# led_circuits.net
KiCad netlist of a schematic drawn in EAGLE
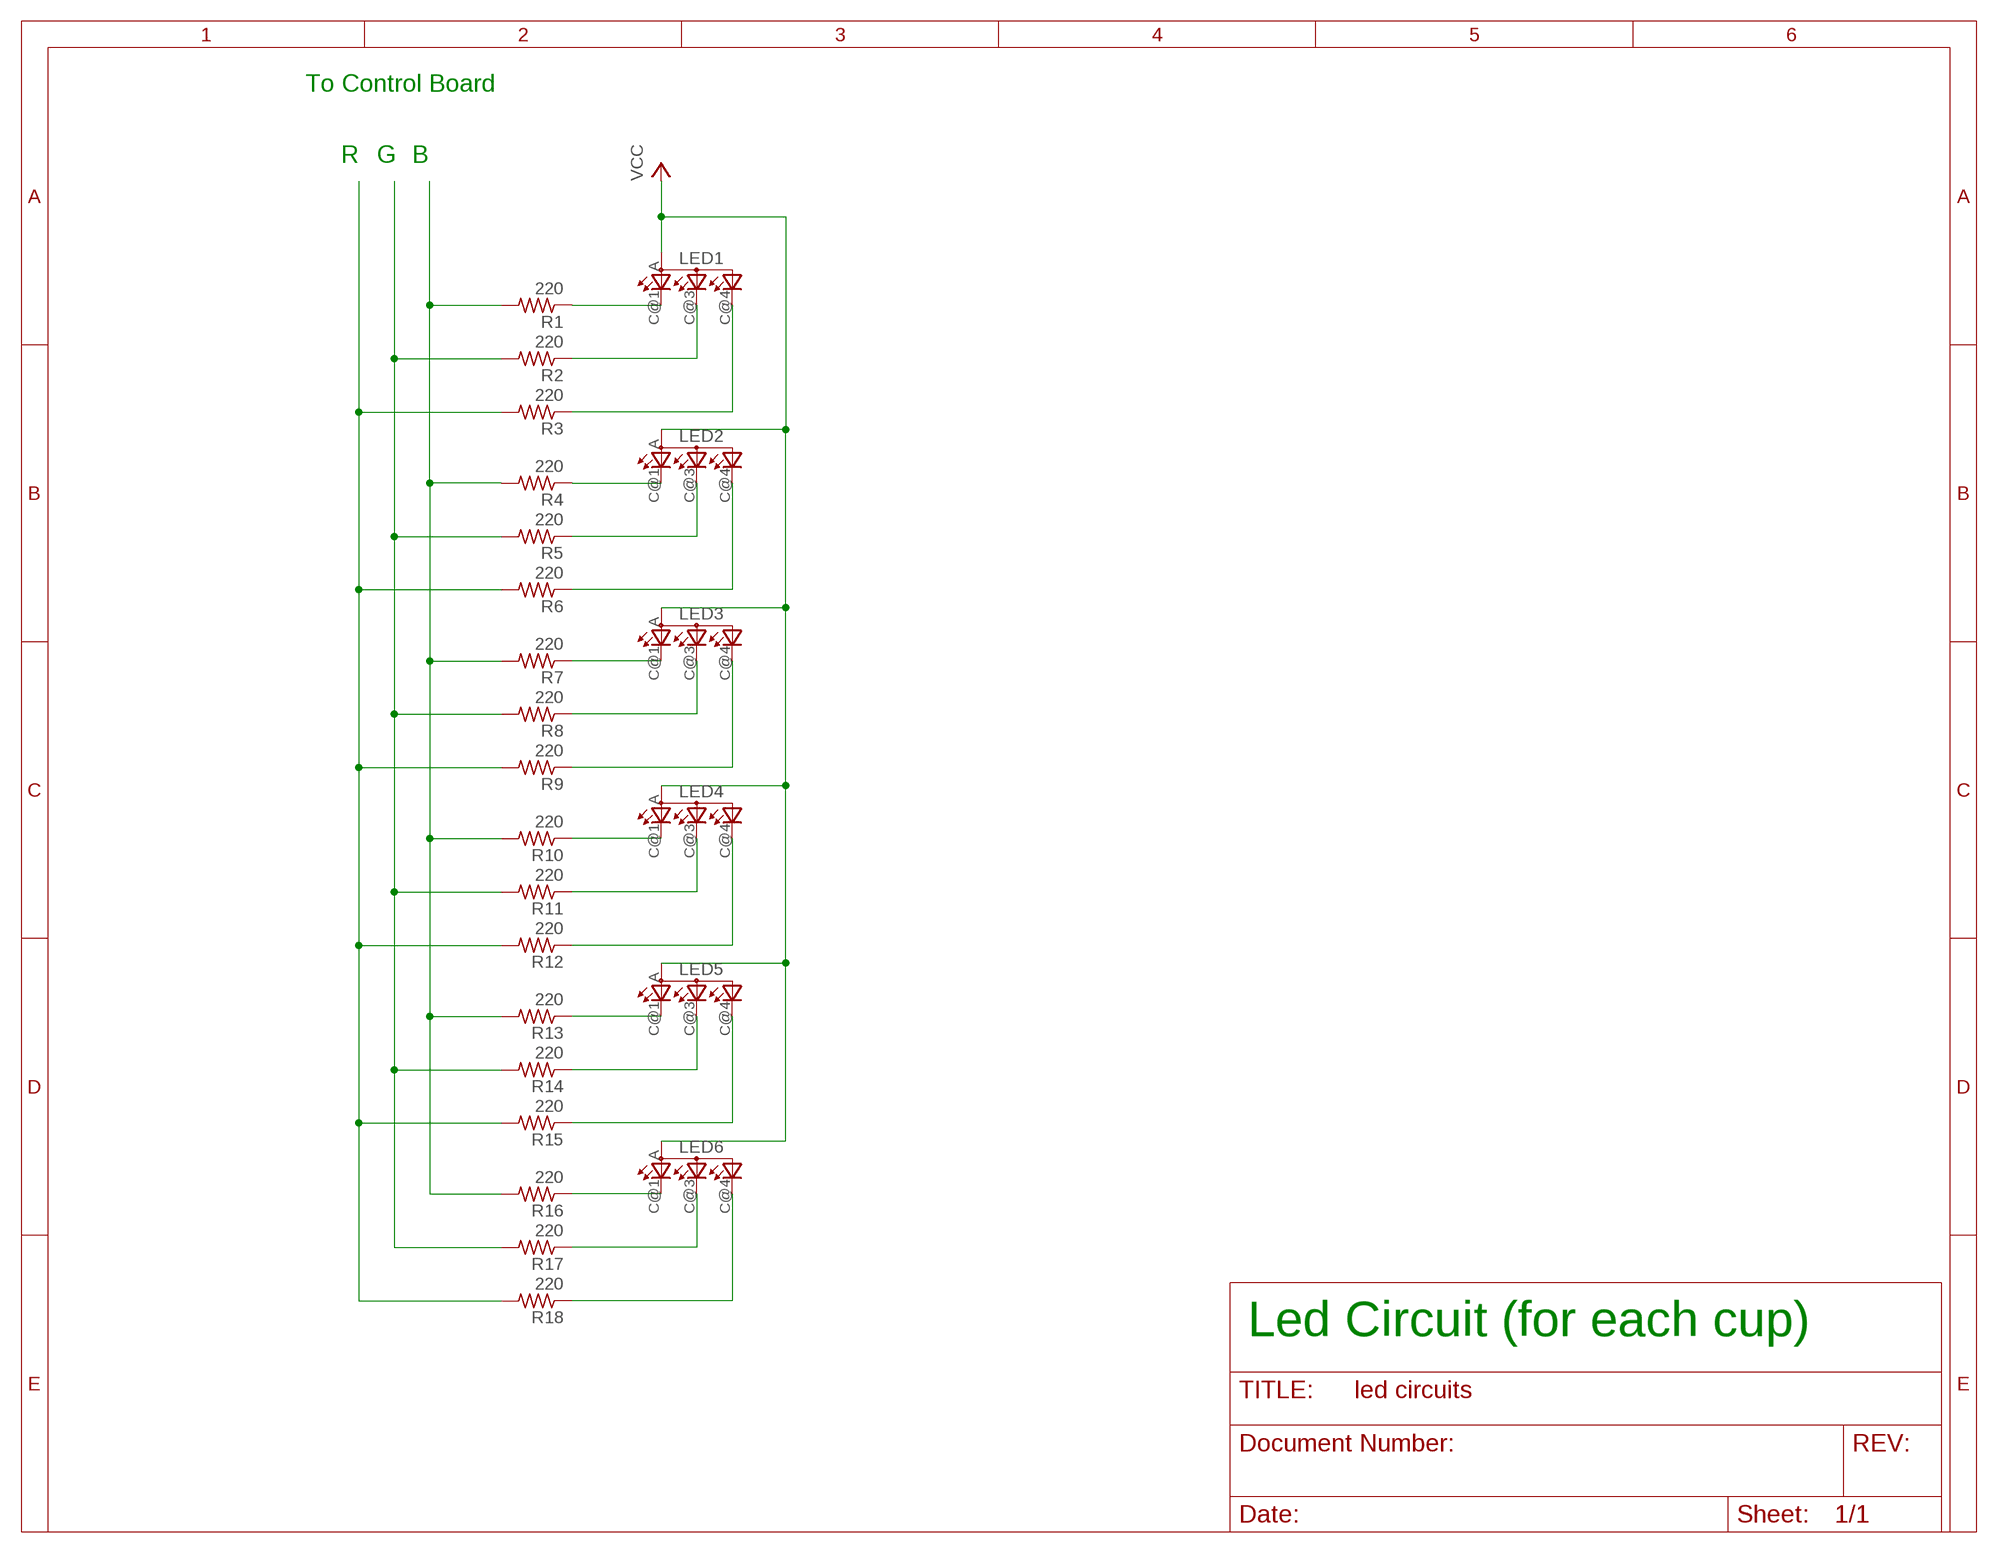
[diagram p0: schematic, sheet 1]

(export (version "E")
  (design (tool "Eeschema 10.0.6"))
  (components
    (comp (ref "LED1")
      (value "TOPLED-3P-LCC-4")
      (footprint "eagle-import:P-LCC-4")
      (libsource (lib "eagle-import") (part "TOPLED-3P-LCC-4"))
    )
    (comp (ref "LED2")
      (value "TOPLED-3P-LCC-4")
      (footprint "eagle-import:P-LCC-4")
      (libsource (lib "eagle-import") (part "TOPLED-3P-LCC-4"))
    )
    (comp (ref "LED3")
      (value "TOPLED-3P-LCC-4")
      (footprint "eagle-import:P-LCC-4")
      (libsource (lib "eagle-import") (part "TOPLED-3P-LCC-4"))
    )
    (comp (ref "LED4")
      (value "TOPLED-3P-LCC-4")
      (footprint "eagle-import:P-LCC-4")
      (libsource (lib "eagle-import") (part "TOPLED-3P-LCC-4"))
    )
    (comp (ref "LED5")
      (value "TOPLED-3P-LCC-4")
      (footprint "eagle-import:P-LCC-4")
      (libsource (lib "eagle-import") (part "TOPLED-3P-LCC-4"))
    )
    (comp (ref "LED6")
      (value "TOPLED-3P-LCC-4")
      (footprint "eagle-import:P-LCC-4")
      (libsource (lib "eagle-import") (part "TOPLED-3P-LCC-4"))
    )
    (comp (ref "R1")
      (value "220")
      (footprint "eagle-import:0207_2V")
      (libsource (lib "eagle-import") (part "R-US_0207/2V"))
    )
    (comp (ref "R2")
      (value "220")
      (footprint "eagle-import:0207_2V")
      (libsource (lib "eagle-import") (part "R-US_0207/2V"))
    )
    (comp (ref "R3")
      (value "220")
      (footprint "eagle-import:0207_2V")
      (libsource (lib "eagle-import") (part "R-US_0207/2V"))
    )
    (comp (ref "R4")
      (value "220")
      (footprint "eagle-import:0207_2V")
      (libsource (lib "eagle-import") (part "R-US_0207/2V"))
    )
    (comp (ref "R5")
      (value "220")
      (footprint "eagle-import:0207_2V")
      (libsource (lib "eagle-import") (part "R-US_0207/2V"))
    )
    (comp (ref "R6")
      (value "220")
      (footprint "eagle-import:0207_2V")
      (libsource (lib "eagle-import") (part "R-US_0207/2V"))
    )
    (comp (ref "R7")
      (value "220")
      (footprint "eagle-import:0207_2V")
      (libsource (lib "eagle-import") (part "R-US_0207/2V"))
    )
    (comp (ref "R8")
      (value "220")
      (footprint "eagle-import:0207_2V")
      (libsource (lib "eagle-import") (part "R-US_0207/2V"))
    )
    (comp (ref "R9")
      (value "220")
      (footprint "eagle-import:0207_2V")
      (libsource (lib "eagle-import") (part "R-US_0207/2V"))
    )
    (comp (ref "R10")
      (value "220")
      (footprint "eagle-import:0207_2V")
      (libsource (lib "eagle-import") (part "R-US_0207/2V"))
    )
    (comp (ref "R11")
      (value "220")
      (footprint "eagle-import:0207_2V")
      (libsource (lib "eagle-import") (part "R-US_0207/2V"))
    )
    (comp (ref "R12")
      (value "220")
      (footprint "eagle-import:0207_2V")
      (libsource (lib "eagle-import") (part "R-US_0207/2V"))
    )
    (comp (ref "R13")
      (value "220")
      (footprint "eagle-import:0207_2V")
      (libsource (lib "eagle-import") (part "R-US_0207/2V"))
    )
    (comp (ref "R14")
      (value "220")
      (footprint "eagle-import:0207_2V")
      (libsource (lib "eagle-import") (part "R-US_0207/2V"))
    )
    (comp (ref "R15")
      (value "220")
      (footprint "eagle-import:0207_2V")
      (libsource (lib "eagle-import") (part "R-US_0207/2V"))
    )
    (comp (ref "R16")
      (value "220")
      (footprint "eagle-import:0207_2V")
      (libsource (lib "eagle-import") (part "R-US_0207/2V"))
    )
    (comp (ref "R17")
      (value "220")
      (footprint "eagle-import:0207_2V")
      (libsource (lib "eagle-import") (part "R-US_0207/2V"))
    )
    (comp (ref "R18")
      (value "220")
      (footprint "eagle-import:0207_2V")
      (libsource (lib "eagle-import") (part "R-US_0207/2V"))
    )
  )
  (nets
    (net (code "1") (name "Net-(LED1-CBLUE)") (class "Default")
      (node (ref "LED1") (pin "C@3") (pinfunction "CBLUE_C@3") (pintype "passive"))
      (node (ref "R2") (pin "1") (pinfunction "1_1") (pintype "passive"))
    )
    (net (code "2") (name "Net-(LED1-CGREEN)") (class "Default")
      (node (ref "LED1") (pin "C@4") (pinfunction "CGREEN_C@4") (pintype "passive"))
      (node (ref "R3") (pin "1") (pinfunction "1_1") (pintype "passive"))
    )
    (net (code "3") (name "Net-(LED1-CRED)") (class "Default")
      (node (ref "LED1") (pin "C@1") (pinfunction "CRED_C@1") (pintype "passive"))
      (node (ref "R1") (pin "1") (pinfunction "1_1") (pintype "passive"))
    )
    (net (code "4") (name "Net-(LED2-CBLUE)") (class "Default")
      (node (ref "LED2") (pin "C@3") (pinfunction "CBLUE_C@3") (pintype "passive"))
      (node (ref "R5") (pin "1") (pinfunction "1_1") (pintype "passive"))
    )
    (net (code "5") (name "Net-(LED2-CGREEN)") (class "Default")
      (node (ref "LED2") (pin "C@4") (pinfunction "CGREEN_C@4") (pintype "passive"))
      (node (ref "R6") (pin "1") (pinfunction "1_1") (pintype "passive"))
    )
    (net (code "6") (name "Net-(LED2-CRED)") (class "Default")
      (node (ref "LED2") (pin "C@1") (pinfunction "CRED_C@1") (pintype "passive"))
      (node (ref "R4") (pin "1") (pinfunction "1_1") (pintype "passive"))
    )
    (net (code "7") (name "Net-(LED3-CBLUE)") (class "Default")
      (node (ref "LED3") (pin "C@3") (pinfunction "CBLUE_C@3") (pintype "passive"))
      (node (ref "R8") (pin "1") (pinfunction "1_1") (pintype "passive"))
    )
    (net (code "8") (name "Net-(LED3-CGREEN)") (class "Default")
      (node (ref "LED3") (pin "C@4") (pinfunction "CGREEN_C@4") (pintype "passive"))
      (node (ref "R9") (pin "1") (pinfunction "1_1") (pintype "passive"))
    )
    (net (code "9") (name "Net-(LED3-CRED)") (class "Default")
      (node (ref "LED3") (pin "C@1") (pinfunction "CRED_C@1") (pintype "passive"))
      (node (ref "R7") (pin "1") (pinfunction "1_1") (pintype "passive"))
    )
    (net (code "10") (name "Net-(LED4-CBLUE)") (class "Default")
      (node (ref "LED4") (pin "C@3") (pinfunction "CBLUE_C@3") (pintype "passive"))
      (node (ref "R11") (pin "1") (pinfunction "1_1") (pintype "passive"))
    )
    (net (code "11") (name "Net-(LED4-CGREEN)") (class "Default")
      (node (ref "LED4") (pin "C@4") (pinfunction "CGREEN_C@4") (pintype "passive"))
      (node (ref "R12") (pin "1") (pinfunction "1_1") (pintype "passive"))
    )
    (net (code "12") (name "Net-(LED4-CRED)") (class "Default")
      (node (ref "LED4") (pin "C@1") (pinfunction "CRED_C@1") (pintype "passive"))
      (node (ref "R10") (pin "1") (pinfunction "1_1") (pintype "passive"))
    )
    (net (code "13") (name "Net-(LED5-CBLUE)") (class "Default")
      (node (ref "LED5") (pin "C@3") (pinfunction "CBLUE_C@3") (pintype "passive"))
      (node (ref "R14") (pin "1") (pinfunction "1_1") (pintype "passive"))
    )
    (net (code "14") (name "Net-(LED5-CGREEN)") (class "Default")
      (node (ref "LED5") (pin "C@4") (pinfunction "CGREEN_C@4") (pintype "passive"))
      (node (ref "R15") (pin "1") (pinfunction "1_1") (pintype "passive"))
    )
    (net (code "15") (name "Net-(LED5-CRED)") (class "Default")
      (node (ref "LED5") (pin "C@1") (pinfunction "CRED_C@1") (pintype "passive"))
      (node (ref "R13") (pin "1") (pinfunction "1_1") (pintype "passive"))
    )
    (net (code "16") (name "Net-(LED6-CBLUE)") (class "Default")
      (node (ref "LED6") (pin "C@3") (pinfunction "CBLUE_C@3") (pintype "passive"))
      (node (ref "R17") (pin "1") (pinfunction "1_1") (pintype "passive"))
    )
    (net (code "17") (name "Net-(LED6-CGREEN)") (class "Default")
      (node (ref "LED6") (pin "C@4") (pinfunction "CGREEN_C@4") (pintype "passive"))
      (node (ref "R18") (pin "1") (pinfunction "1_1") (pintype "passive"))
    )
    (net (code "18") (name "Net-(LED6-CRED)") (class "Default")
      (node (ref "LED6") (pin "C@1") (pinfunction "CRED_C@1") (pintype "passive"))
      (node (ref "R16") (pin "1") (pinfunction "1_1") (pintype "passive"))
    )
    (net (code "19") (name "Net-(R1-Pad2)") (class "Default")
      (node (ref "R1") (pin "2") (pinfunction "2_2") (pintype "passive"))
      (node (ref "R10") (pin "2") (pinfunction "2_2") (pintype "passive"))
      (node (ref "R13") (pin "2") (pinfunction "2_2") (pintype "passive"))
      (node (ref "R16") (pin "2") (pinfunction "2_2") (pintype "passive"))
      (node (ref "R4") (pin "2") (pinfunction "2_2") (pintype "passive"))
      (node (ref "R7") (pin "2") (pinfunction "2_2") (pintype "passive"))
    )
    (net (code "20") (name "Net-(R11-Pad2)") (class "Default")
      (node (ref "R11") (pin "2") (pinfunction "2_2") (pintype "passive"))
      (node (ref "R14") (pin "2") (pinfunction "2_2") (pintype "passive"))
      (node (ref "R17") (pin "2") (pinfunction "2_2") (pintype "passive"))
      (node (ref "R2") (pin "2") (pinfunction "2_2") (pintype "passive"))
      (node (ref "R5") (pin "2") (pinfunction "2_2") (pintype "passive"))
      (node (ref "R8") (pin "2") (pinfunction "2_2") (pintype "passive"))
    )
    (net (code "21") (name "Net-(R12-Pad2)") (class "Default")
      (node (ref "R12") (pin "2") (pinfunction "2_2") (pintype "passive"))
      (node (ref "R15") (pin "2") (pinfunction "2_2") (pintype "passive"))
      (node (ref "R18") (pin "2") (pinfunction "2_2") (pintype "passive"))
      (node (ref "R3") (pin "2") (pinfunction "2_2") (pintype "passive"))
      (node (ref "R6") (pin "2") (pinfunction "2_2") (pintype "passive"))
      (node (ref "R9") (pin "2") (pinfunction "2_2") (pintype "passive"))
    )
    (net (code "22") (name "VCC") (class "Default")
      (node (ref "LED1") (pin "A") (pinfunction "A2_A") (pintype "passive"))
      (node (ref "LED2") (pin "A") (pinfunction "A2_A") (pintype "passive"))
      (node (ref "LED3") (pin "A") (pinfunction "A2_A") (pintype "passive"))
      (node (ref "LED4") (pin "A") (pinfunction "A2_A") (pintype "passive"))
      (node (ref "LED5") (pin "A") (pinfunction "A2_A") (pintype "passive"))
      (node (ref "LED6") (pin "A") (pinfunction "A2_A") (pintype "passive"))
    )
  )
)
